# spectrum_analyzer.net
KiCad netlist of a schematic drawn in EAGLE
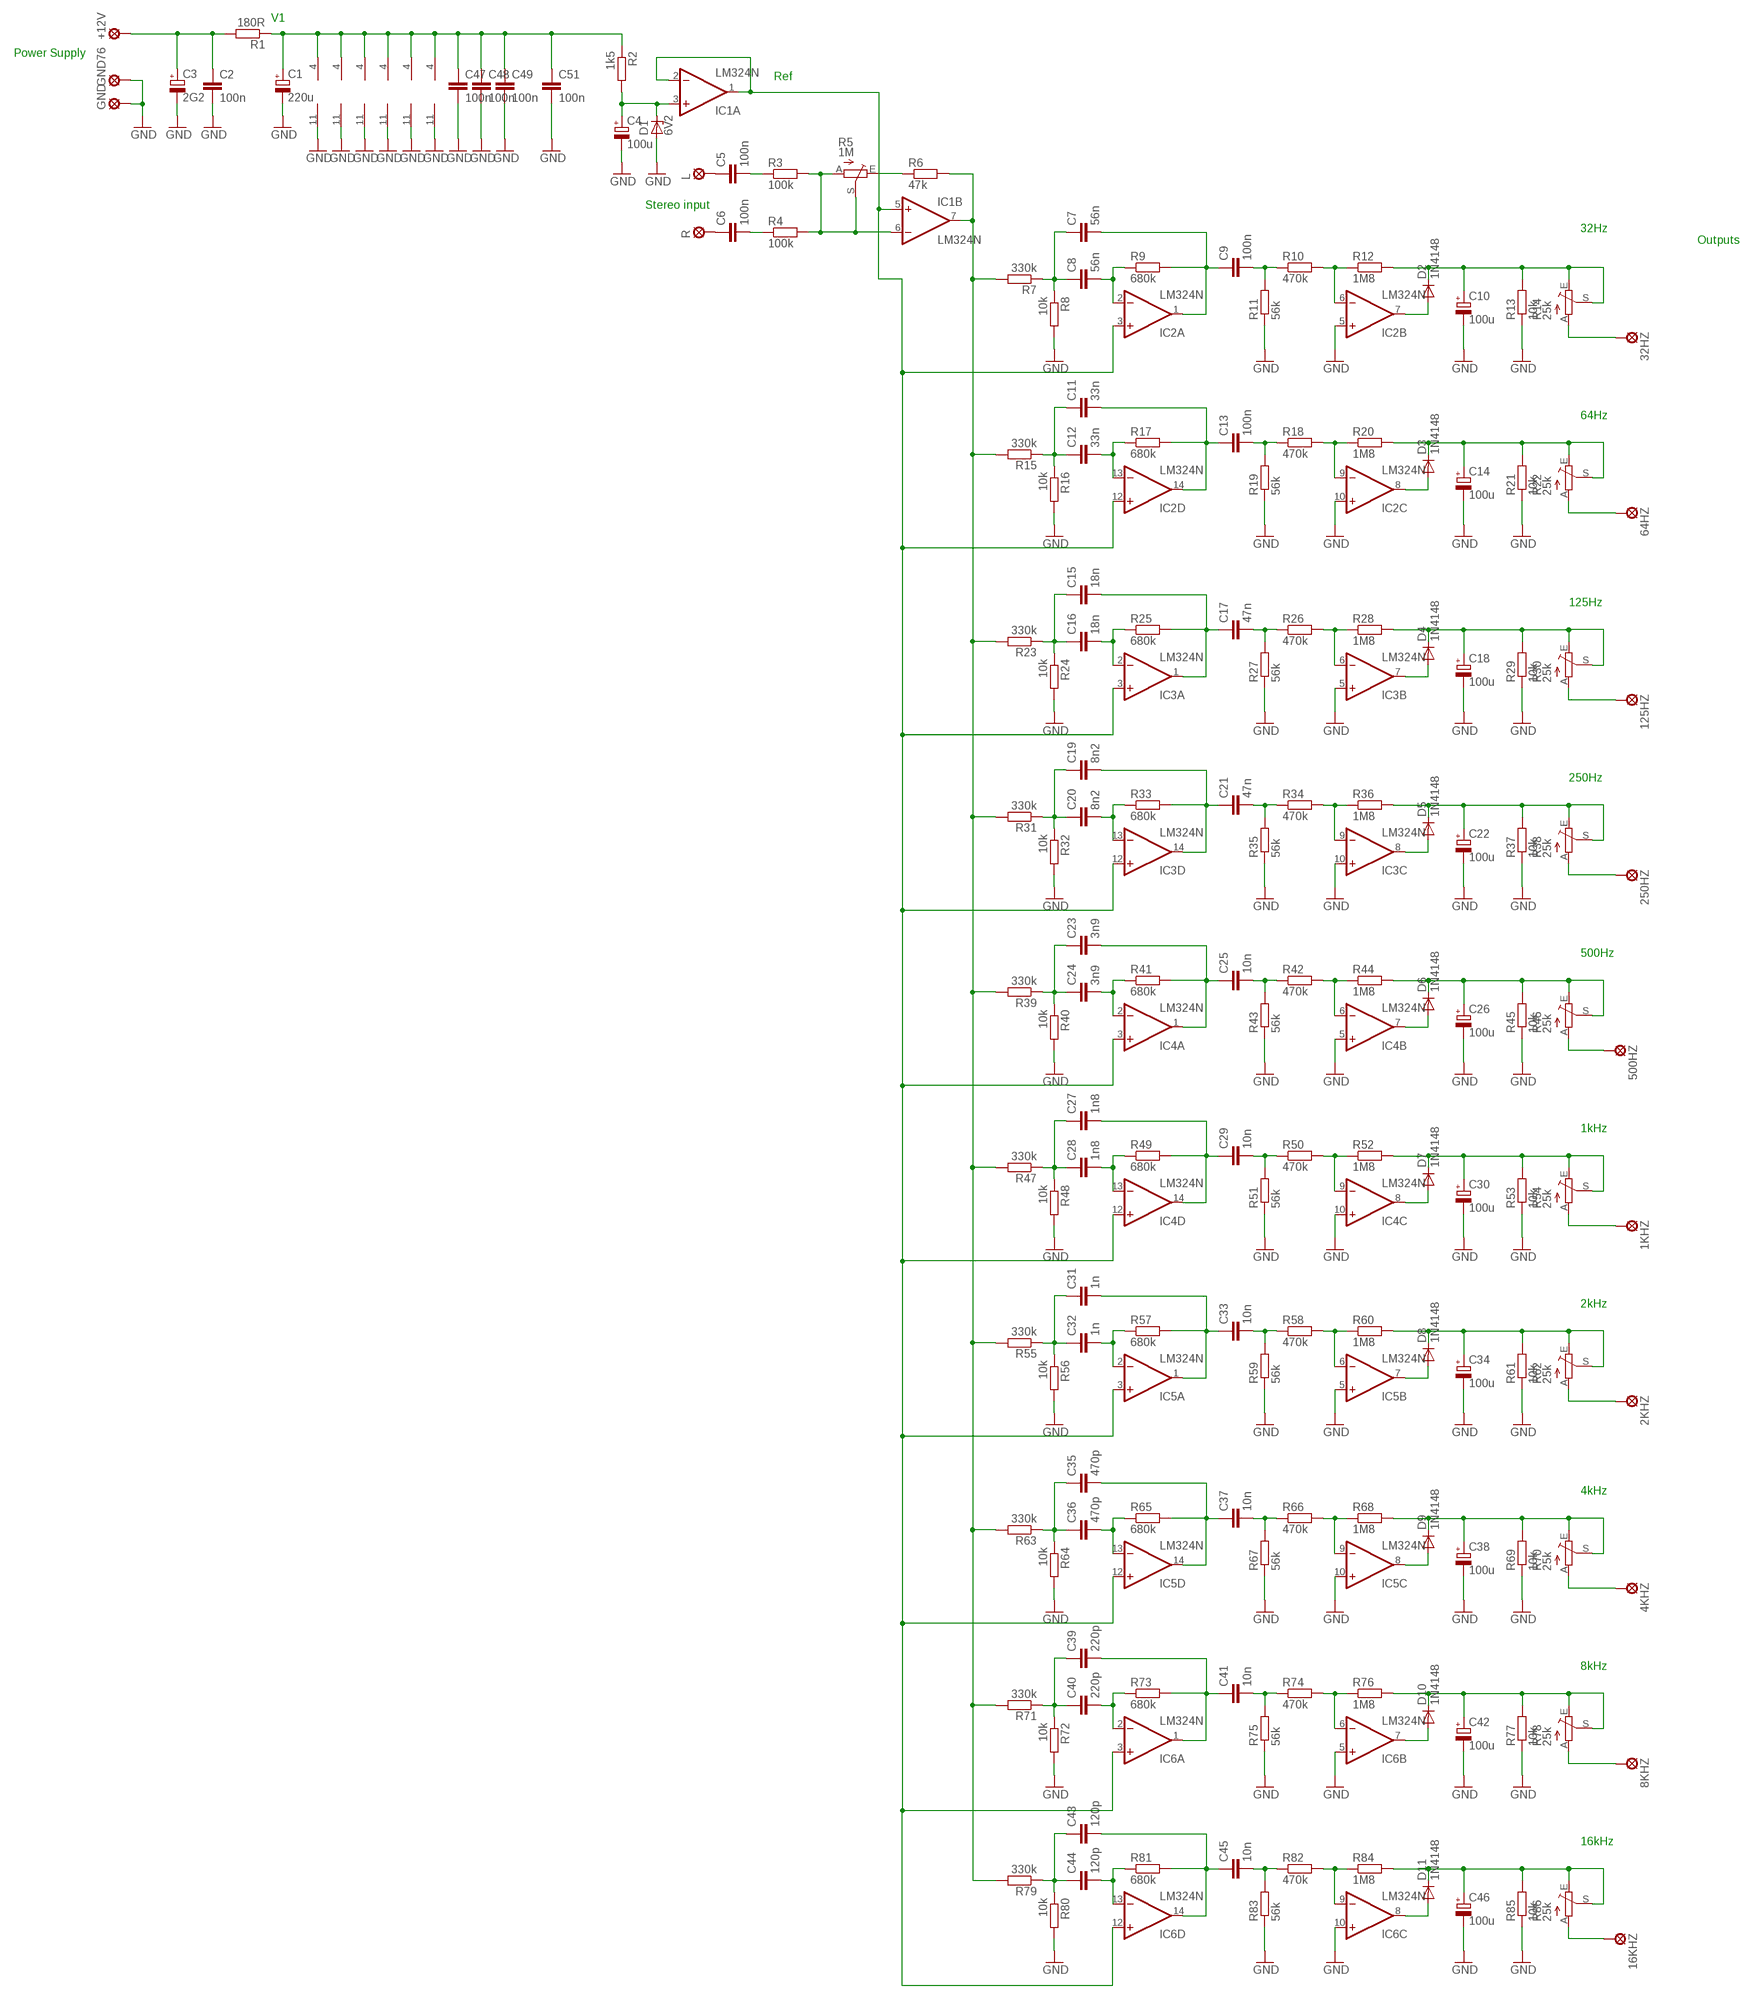
[diagram p0: schematic, sheet 1]

(export (version "E")
  (design (tool "Eeschema 10.0.6"))
  (components
    (comp (ref "+12V")
      (value "LSP10")
      (footprint "eagle-import:LSP10")
      (libsource (lib "eagle-import") (part "LSP10"))
    )
    (comp (ref "1KHZ")
      (value "LSP10")
      (footprint "eagle-import:LSP10")
      (libsource (lib "eagle-import") (part "LSP10"))
    )
    (comp (ref "2KHZ")
      (value "LSP10")
      (footprint "eagle-import:LSP10")
      (libsource (lib "eagle-import") (part "LSP10"))
    )
    (comp (ref "4KHZ")
      (value "LSP10")
      (footprint "eagle-import:LSP10")
      (libsource (lib "eagle-import") (part "LSP10"))
    )
    (comp (ref "8KHZ")
      (value "LSP10")
      (footprint "eagle-import:LSP10")
      (libsource (lib "eagle-import") (part "LSP10"))
    )
    (comp (ref "16KHZ")
      (value "LSP10")
      (footprint "eagle-import:LSP10")
      (libsource (lib "eagle-import") (part "LSP10"))
    )
    (comp (ref "32HZ")
      (value "LSP10")
      (footprint "eagle-import:LSP10")
      (libsource (lib "eagle-import") (part "LSP10"))
    )
    (comp (ref "64HZ")
      (value "LSP10")
      (footprint "eagle-import:LSP10")
      (libsource (lib "eagle-import") (part "LSP10"))
    )
    (comp (ref "125HZ")
      (value "LSP10")
      (footprint "eagle-import:LSP10")
      (libsource (lib "eagle-import") (part "LSP10"))
    )
    (comp (ref "250HZ")
      (value "LSP10")
      (footprint "eagle-import:LSP10")
      (libsource (lib "eagle-import") (part "LSP10"))
    )
    (comp (ref "500HZ")
      (value "LSP10")
      (footprint "eagle-import:LSP10")
      (libsource (lib "eagle-import") (part "LSP10"))
    )
    (comp (ref "C1")
      (value "220u")
      (footprint "eagle-import:E2,5-7")
      (libsource (lib "eagle-import") (part "CPOL-EUE2.5-7"))
    )
    (comp (ref "C2")
      (value "100n")
      (footprint "eagle-import:C050-025X075")
      (libsource (lib "eagle-import") (part "C-EU050-025X075"))
    )
    (comp (ref "C3")
      (value "2G2")
      (footprint "eagle-import:E5-10,5")
      (libsource (lib "eagle-import") (part "CPOL-EUE5-10.5"))
    )
    (comp (ref "C4")
      (value "100u")
      (footprint "eagle-import:E2,5-7")
      (libsource (lib "eagle-import") (part "CPOL-EUE2.5-7"))
    )
    (comp (ref "C5")
      (value "100n")
      (footprint "eagle-import:C050-025X075")
      (libsource (lib "eagle-import") (part "C-EU050-025X075"))
    )
    (comp (ref "C6")
      (value "100n")
      (footprint "eagle-import:C050-025X075")
      (libsource (lib "eagle-import") (part "C-EU050-025X075"))
    )
    (comp (ref "C7")
      (value "56n")
      (footprint "eagle-import:C050-025X075")
      (libsource (lib "eagle-import") (part "C-EU050-025X075"))
    )
    (comp (ref "C8")
      (value "56n")
      (footprint "eagle-import:C050-025X075")
      (libsource (lib "eagle-import") (part "C-EU050-025X075"))
    )
    (comp (ref "C9")
      (value "100n")
      (footprint "eagle-import:C050-025X075")
      (libsource (lib "eagle-import") (part "C-EU050-025X075"))
    )
    (comp (ref "C10")
      (value "100u")
      (footprint "eagle-import:E2,5-7")
      (libsource (lib "eagle-import") (part "CPOL-EUE2.5-7"))
    )
    (comp (ref "C11")
      (value "33n")
      (footprint "eagle-import:C050-025X075")
      (libsource (lib "eagle-import") (part "C-EU050-025X075"))
    )
    (comp (ref "C12")
      (value "33n")
      (footprint "eagle-import:C050-025X075")
      (libsource (lib "eagle-import") (part "C-EU050-025X075"))
    )
    (comp (ref "C13")
      (value "100n")
      (footprint "eagle-import:C050-025X075")
      (libsource (lib "eagle-import") (part "C-EU050-025X075"))
    )
    (comp (ref "C14")
      (value "100u")
      (footprint "eagle-import:E2,5-7")
      (libsource (lib "eagle-import") (part "CPOL-EUE2.5-7"))
    )
    (comp (ref "C15")
      (value "18n")
      (footprint "eagle-import:C050-025X075")
      (libsource (lib "eagle-import") (part "C-EU050-025X075"))
    )
    (comp (ref "C16")
      (value "18n")
      (footprint "eagle-import:C050-025X075")
      (libsource (lib "eagle-import") (part "C-EU050-025X075"))
    )
    (comp (ref "C17")
      (value "47n")
      (footprint "eagle-import:C050-025X075")
      (libsource (lib "eagle-import") (part "C-EU050-025X075"))
    )
    (comp (ref "C18")
      (value "100u")
      (footprint "eagle-import:E2,5-7")
      (libsource (lib "eagle-import") (part "CPOL-EUE2.5-7"))
    )
    (comp (ref "C19")
      (value "8n2")
      (footprint "eagle-import:C050-025X075")
      (libsource (lib "eagle-import") (part "C-EU050-025X075"))
    )
    (comp (ref "C20")
      (value "8n2")
      (footprint "eagle-import:C050-025X075")
      (libsource (lib "eagle-import") (part "C-EU050-025X075"))
    )
    (comp (ref "C21")
      (value "47n")
      (footprint "eagle-import:C050-025X075")
      (libsource (lib "eagle-import") (part "C-EU050-025X075"))
    )
    (comp (ref "C22")
      (value "100u")
      (footprint "eagle-import:E2,5-7")
      (libsource (lib "eagle-import") (part "CPOL-EUE2.5-7"))
    )
    (comp (ref "C23")
      (value "3n9")
      (footprint "eagle-import:C050-025X075")
      (libsource (lib "eagle-import") (part "C-EU050-025X075"))
    )
    (comp (ref "C24")
      (value "3n9")
      (footprint "eagle-import:C050-025X075")
      (libsource (lib "eagle-import") (part "C-EU050-025X075"))
    )
    (comp (ref "C25")
      (value "10n")
      (footprint "eagle-import:C050-025X075")
      (libsource (lib "eagle-import") (part "C-EU050-025X075"))
    )
    (comp (ref "C26")
      (value "100u")
      (footprint "eagle-import:E2,5-7")
      (libsource (lib "eagle-import") (part "CPOL-EUE2.5-7"))
    )
    (comp (ref "C27")
      (value "1n8")
      (footprint "eagle-import:C050-025X075")
      (libsource (lib "eagle-import") (part "C-EU050-025X075"))
    )
    (comp (ref "C28")
      (value "1n8")
      (footprint "eagle-import:C050-025X075")
      (libsource (lib "eagle-import") (part "C-EU050-025X075"))
    )
    (comp (ref "C29")
      (value "10n")
      (footprint "eagle-import:C050-025X075")
      (libsource (lib "eagle-import") (part "C-EU050-025X075"))
    )
    (comp (ref "C30")
      (value "100u")
      (footprint "eagle-import:E2,5-7")
      (libsource (lib "eagle-import") (part "CPOL-EUE2.5-7"))
    )
    (comp (ref "C31")
      (value "1n")
      (footprint "eagle-import:C050-025X075")
      (libsource (lib "eagle-import") (part "C-EU050-025X075"))
    )
    (comp (ref "C32")
      (value "1n")
      (footprint "eagle-import:C050-025X075")
      (libsource (lib "eagle-import") (part "C-EU050-025X075"))
    )
    (comp (ref "C33")
      (value "10n")
      (footprint "eagle-import:C050-025X075")
      (libsource (lib "eagle-import") (part "C-EU050-025X075"))
    )
    (comp (ref "C34")
      (value "100u")
      (footprint "eagle-import:E2,5-7")
      (libsource (lib "eagle-import") (part "CPOL-EUE2.5-7"))
    )
    (comp (ref "C35")
      (value "470p")
      (footprint "eagle-import:C050-025X075")
      (libsource (lib "eagle-import") (part "C-EU050-025X075"))
    )
    (comp (ref "C36")
      (value "470p")
      (footprint "eagle-import:C050-025X075")
      (libsource (lib "eagle-import") (part "C-EU050-025X075"))
    )
    (comp (ref "C37")
      (value "10n")
      (footprint "eagle-import:C050-025X075")
      (libsource (lib "eagle-import") (part "C-EU050-025X075"))
    )
    (comp (ref "C38")
      (value "100u")
      (footprint "eagle-import:E2,5-7")
      (libsource (lib "eagle-import") (part "CPOL-EUE2.5-7"))
    )
    (comp (ref "C39")
      (value "220p")
      (footprint "eagle-import:C050-025X075")
      (libsource (lib "eagle-import") (part "C-EU050-025X075"))
    )
    (comp (ref "C40")
      (value "220p")
      (footprint "eagle-import:C050-025X075")
      (libsource (lib "eagle-import") (part "C-EU050-025X075"))
    )
    (comp (ref "C41")
      (value "10n")
      (footprint "eagle-import:C050-025X075")
      (libsource (lib "eagle-import") (part "C-EU050-025X075"))
    )
    (comp (ref "C42")
      (value "100u")
      (footprint "eagle-import:E2,5-7")
      (libsource (lib "eagle-import") (part "CPOL-EUE2.5-7"))
    )
    (comp (ref "C43")
      (value "120p")
      (footprint "eagle-import:C050-025X075")
      (libsource (lib "eagle-import") (part "C-EU050-025X075"))
    )
    (comp (ref "C44")
      (value "120p")
      (footprint "eagle-import:C050-025X075")
      (libsource (lib "eagle-import") (part "C-EU050-025X075"))
    )
    (comp (ref "C45")
      (value "10n")
      (footprint "eagle-import:C050-025X075")
      (libsource (lib "eagle-import") (part "C-EU050-025X075"))
    )
    (comp (ref "C46")
      (value "100u")
      (footprint "eagle-import:E2,5-7")
      (libsource (lib "eagle-import") (part "CPOL-EUE2.5-7"))
    )
    (comp (ref "C47")
      (value "100n")
      (footprint "eagle-import:C050-025X075")
      (libsource (lib "eagle-import") (part "C-EU050-025X075"))
    )
    (comp (ref "C48")
      (value "100n")
      (footprint "eagle-import:C050-025X075")
      (libsource (lib "eagle-import") (part "C-EU050-025X075"))
    )
    (comp (ref "C49")
      (value "100n")
      (footprint "eagle-import:C050-025X075")
      (libsource (lib "eagle-import") (part "C-EU050-025X075"))
    )
    (comp (ref "C51")
      (value "100n")
      (footprint "eagle-import:C050-025X075")
      (libsource (lib "eagle-import") (part "C-EU050-025X075"))
    )
    (comp (ref "D1")
      (value "6V2")
      (footprint "eagle-import:DO35Z10")
      (libsource (lib "eagle-import") (part "1N821"))
    )
    (comp (ref "D2")
      (value "1N4148")
      (footprint "eagle-import:DO35-10")
      (libsource (lib "eagle-import") (part "1N4148DO35-10"))
    )
    (comp (ref "D3")
      (value "1N4148")
      (footprint "eagle-import:DO35-10")
      (libsource (lib "eagle-import") (part "1N4148DO35-10"))
    )
    (comp (ref "D4")
      (value "1N4148")
      (footprint "eagle-import:DO35-10")
      (libsource (lib "eagle-import") (part "1N4148DO35-10"))
    )
    (comp (ref "D5")
      (value "1N4148")
      (footprint "eagle-import:DO35-10")
      (libsource (lib "eagle-import") (part "1N4148DO35-10"))
    )
    (comp (ref "D6")
      (value "1N4148")
      (footprint "eagle-import:DO35-10")
      (libsource (lib "eagle-import") (part "1N4148DO35-10"))
    )
    (comp (ref "D7")
      (value "1N4148")
      (footprint "eagle-import:DO35-10")
      (libsource (lib "eagle-import") (part "1N4148DO35-10"))
    )
    (comp (ref "D8")
      (value "1N4148")
      (footprint "eagle-import:DO35-10")
      (libsource (lib "eagle-import") (part "1N4148DO35-10"))
    )
    (comp (ref "D9")
      (value "1N4148")
      (footprint "eagle-import:DO35-10")
      (libsource (lib "eagle-import") (part "1N4148DO35-10"))
    )
    (comp (ref "D10")
      (value "1N4148")
      (footprint "eagle-import:DO35-10")
      (libsource (lib "eagle-import") (part "1N4148DO35-10"))
    )
    (comp (ref "D11")
      (value "1N4148")
      (footprint "eagle-import:DO35-10")
      (libsource (lib "eagle-import") (part "1N4148DO35-10"))
    )
    (comp (ref "GND")
      (value "LSP10")
      (footprint "eagle-import:LSP10")
      (libsource (lib "eagle-import") (part "LSP10"))
    )
    (comp (ref "GND76")
      (value "LSP10")
      (footprint "eagle-import:LSP10")
      (libsource (lib "eagle-import") (part "LSP10"))
    )
    (comp (ref "IC1")
      (value "LM324N")
      (footprint "eagle-import:DIL14")
      (libsource (lib "eagle-import") (part "LM324N"))
    )
    (comp (ref "IC2")
      (value "LM324N")
      (footprint "eagle-import:DIL14")
      (libsource (lib "eagle-import") (part "LM324N"))
    )
    (comp (ref "IC3")
      (value "LM324N")
      (footprint "eagle-import:DIL14")
      (libsource (lib "eagle-import") (part "LM324N"))
    )
    (comp (ref "IC4")
      (value "LM324N")
      (footprint "eagle-import:DIL14")
      (libsource (lib "eagle-import") (part "LM324N"))
    )
    (comp (ref "IC5")
      (value "LM324N")
      (footprint "eagle-import:DIL14")
      (libsource (lib "eagle-import") (part "LM324N"))
    )
    (comp (ref "IC6")
      (value "LM324N")
      (footprint "eagle-import:DIL14")
      (libsource (lib "eagle-import") (part "LM324N"))
    )
    (comp (ref "L")
      (value "LSP10")
      (footprint "eagle-import:LSP10")
      (libsource (lib "eagle-import") (part "LSP10"))
    )
    (comp (ref "R")
      (value "LSP10")
      (footprint "eagle-import:LSP10")
      (libsource (lib "eagle-import") (part "LSP10"))
    )
    (comp (ref "R1")
      (value "180R")
      (footprint "eagle-import:0207_10")
      (libsource (lib "eagle-import") (part "R-EU_0207/10"))
    )
    (comp (ref "R2")
      (value "1k5")
      (footprint "eagle-import:0207_10")
      (libsource (lib "eagle-import") (part "R-EU_0207/10"))
    )
    (comp (ref "R3")
      (value "100k")
      (footprint "eagle-import:0207_10")
      (libsource (lib "eagle-import") (part "R-EU_0207/10"))
    )
    (comp (ref "R4")
      (value "100k")
      (footprint "eagle-import:0207_10")
      (libsource (lib "eagle-import") (part "R-EU_0207/10"))
    )
    (comp (ref "R5")
      (value "1M")
      (footprint "eagle-import:CA6V")
      (libsource (lib "eagle-import") (part "TRIM_EU-CA6V"))
    )
    (comp (ref "R6")
      (value "47k")
      (footprint "eagle-import:0207_10")
      (libsource (lib "eagle-import") (part "R-EU_0207/10"))
    )
    (comp (ref "R7")
      (value "330k")
      (footprint "eagle-import:0207_10")
      (libsource (lib "eagle-import") (part "R-EU_0207/10"))
    )
    (comp (ref "R8")
      (value "10k")
      (footprint "eagle-import:0207_10")
      (libsource (lib "eagle-import") (part "R-EU_0207/10"))
    )
    (comp (ref "R9")
      (value "680k")
      (footprint "eagle-import:0207_10")
      (libsource (lib "eagle-import") (part "R-EU_0207/10"))
    )
    (comp (ref "R10")
      (value "470k")
      (footprint "eagle-import:0207_10")
      (libsource (lib "eagle-import") (part "R-EU_0207/10"))
    )
    (comp (ref "R11")
      (value "56k")
      (footprint "eagle-import:0207_10")
      (libsource (lib "eagle-import") (part "R-EU_0207/10"))
    )
    (comp (ref "R12")
      (value "1M8")
      (footprint "eagle-import:0207_10")
      (libsource (lib "eagle-import") (part "R-EU_0207/10"))
    )
    (comp (ref "R13")
      (value "10k")
      (footprint "eagle-import:0207_10")
      (libsource (lib "eagle-import") (part "R-EU_0207/10"))
    )
    (comp (ref "R14")
      (value "25k")
      (footprint "eagle-import:CA6V")
      (libsource (lib "eagle-import") (part "TRIM_EU-CA6V"))
    )
    (comp (ref "R15")
      (value "330k")
      (footprint "eagle-import:0207_10")
      (libsource (lib "eagle-import") (part "R-EU_0207/10"))
    )
    (comp (ref "R16")
      (value "10k")
      (footprint "eagle-import:0207_10")
      (libsource (lib "eagle-import") (part "R-EU_0207/10"))
    )
    (comp (ref "R17")
      (value "680k")
      (footprint "eagle-import:0207_10")
      (libsource (lib "eagle-import") (part "R-EU_0207/10"))
    )
    (comp (ref "R18")
      (value "470k")
      (footprint "eagle-import:0207_10")
      (libsource (lib "eagle-import") (part "R-EU_0207/10"))
    )
    (comp (ref "R19")
      (value "56k")
      (footprint "eagle-import:0207_10")
      (libsource (lib "eagle-import") (part "R-EU_0207/10"))
    )
    (comp (ref "R20")
      (value "1M8")
      (footprint "eagle-import:0207_10")
      (libsource (lib "eagle-import") (part "R-EU_0207/10"))
    )
    (comp (ref "R21")
      (value "10k")
      (footprint "eagle-import:0207_10")
      (libsource (lib "eagle-import") (part "R-EU_0207/10"))
    )
    (comp (ref "R22")
      (value "25k")
      (footprint "eagle-import:CA6V")
      (libsource (lib "eagle-import") (part "TRIM_EU-CA6V"))
    )
    (comp (ref "R23")
      (value "330k")
      (footprint "eagle-import:0207_10")
      (libsource (lib "eagle-import") (part "R-EU_0207/10"))
    )
    (comp (ref "R24")
      (value "10k")
      (footprint "eagle-import:0207_10")
      (libsource (lib "eagle-import") (part "R-EU_0207/10"))
    )
    (comp (ref "R25")
      (value "680k")
      (footprint "eagle-import:0207_10")
      (libsource (lib "eagle-import") (part "R-EU_0207/10"))
    )
    (comp (ref "R26")
      (value "470k")
      (footprint "eagle-import:0207_10")
      (libsource (lib "eagle-import") (part "R-EU_0207/10"))
    )
    (comp (ref "R27")
      (value "56k")
      (footprint "eagle-import:0207_10")
      (libsource (lib "eagle-import") (part "R-EU_0207/10"))
    )
    (comp (ref "R28")
      (value "1M8")
      (footprint "eagle-import:0207_10")
      (libsource (lib "eagle-import") (part "R-EU_0207/10"))
    )
    (comp (ref "R29")
      (value "10k")
      (footprint "eagle-import:0207_10")
      (libsource (lib "eagle-import") (part "R-EU_0207/10"))
    )
    (comp (ref "R30")
      (value "25k")
      (footprint "eagle-import:CA6V")
      (libsource (lib "eagle-import") (part "TRIM_EU-CA6V"))
    )
    (comp (ref "R31")
      (value "330k")
      (footprint "eagle-import:0207_10")
      (libsource (lib "eagle-import") (part "R-EU_0207/10"))
    )
    (comp (ref "R32")
      (value "10k")
      (footprint "eagle-import:0207_10")
      (libsource (lib "eagle-import") (part "R-EU_0207/10"))
    )
    (comp (ref "R33")
      (value "680k")
      (footprint "eagle-import:0207_10")
      (libsource (lib "eagle-import") (part "R-EU_0207/10"))
    )
    (comp (ref "R34")
      (value "470k")
      (footprint "eagle-import:0207_10")
      (libsource (lib "eagle-import") (part "R-EU_0207/10"))
    )
    (comp (ref "R35")
      (value "56k")
      (footprint "eagle-import:0207_10")
      (libsource (lib "eagle-import") (part "R-EU_0207/10"))
    )
    (comp (ref "R36")
      (value "1M8")
      (footprint "eagle-import:0207_10")
      (libsource (lib "eagle-import") (part "R-EU_0207/10"))
    )
    (comp (ref "R37")
      (value "10k")
      (footprint "eagle-import:0207_10")
      (libsource (lib "eagle-import") (part "R-EU_0207/10"))
    )
    (comp (ref "R38")
      (value "25k")
      (footprint "eagle-import:CA6V")
      (libsource (lib "eagle-import") (part "TRIM_EU-CA6V"))
    )
    (comp (ref "R39")
      (value "330k")
      (footprint "eagle-import:0207_10")
      (libsource (lib "eagle-import") (part "R-EU_0207/10"))
    )
    (comp (ref "R40")
      (value "10k")
      (footprint "eagle-import:0207_10")
      (libsource (lib "eagle-import") (part "R-EU_0207/10"))
    )
    (comp (ref "R41")
      (value "680k")
      (footprint "eagle-import:0207_10")
      (libsource (lib "eagle-import") (part "R-EU_0207/10"))
    )
    (comp (ref "R42")
      (value "470k")
      (footprint "eagle-import:0207_10")
      (libsource (lib "eagle-import") (part "R-EU_0207/10"))
    )
    (comp (ref "R43")
      (value "56k")
      (footprint "eagle-import:0207_10")
      (libsource (lib "eagle-import") (part "R-EU_0207/10"))
    )
    (comp (ref "R44")
      (value "1M8")
      (footprint "eagle-import:0207_10")
      (libsource (lib "eagle-import") (part "R-EU_0207/10"))
    )
    (comp (ref "R45")
      (value "10k")
      (footprint "eagle-import:0207_10")
      (libsource (lib "eagle-import") (part "R-EU_0207/10"))
    )
    (comp (ref "R46")
      (value "25k")
      (footprint "eagle-import:CA6V")
      (libsource (lib "eagle-import") (part "TRIM_EU-CA6V"))
    )
    (comp (ref "R47")
      (value "330k")
      (footprint "eagle-import:0207_10")
      (libsource (lib "eagle-import") (part "R-EU_0207/10"))
    )
    (comp (ref "R48")
      (value "10k")
      (footprint "eagle-import:0207_10")
      (libsource (lib "eagle-import") (part "R-EU_0207/10"))
    )
    (comp (ref "R49")
      (value "680k")
      (footprint "eagle-import:0207_10")
      (libsource (lib "eagle-import") (part "R-EU_0207/10"))
    )
    (comp (ref "R50")
      (value "470k")
      (footprint "eagle-import:0207_10")
      (libsource (lib "eagle-import") (part "R-EU_0207/10"))
    )
    (comp (ref "R51")
      (value "56k")
      (footprint "eagle-import:0207_10")
      (libsource (lib "eagle-import") (part "R-EU_0207/10"))
    )
    (comp (ref "R52")
      (value "1M8")
      (footprint "eagle-import:0207_10")
      (libsource (lib "eagle-import") (part "R-EU_0207/10"))
    )
    (comp (ref "R53")
      (value "10k")
      (footprint "eagle-import:0207_10")
      (libsource (lib "eagle-import") (part "R-EU_0207/10"))
    )
    (comp (ref "R54")
      (value "25k")
      (footprint "eagle-import:CA6V")
      (libsource (lib "eagle-import") (part "TRIM_EU-CA6V"))
    )
    (comp (ref "R55")
      (value "330k")
      (footprint "eagle-import:0207_10")
      (libsource (lib "eagle-import") (part "R-EU_0207/10"))
    )
    (comp (ref "R56")
      (value "10k")
      (footprint "eagle-import:0207_10")
      (libsource (lib "eagle-import") (part "R-EU_0207/10"))
    )
    (comp (ref "R57")
      (value "680k")
      (footprint "eagle-import:0207_10")
      (libsource (lib "eagle-import") (part "R-EU_0207/10"))
    )
    (comp (ref "R58")
      (value "470k")
      (footprint "eagle-import:0207_10")
      (libsource (lib "eagle-import") (part "R-EU_0207/10"))
    )
    (comp (ref "R59")
      (value "56k")
      (footprint "eagle-import:0207_10")
      (libsource (lib "eagle-import") (part "R-EU_0207/10"))
    )
    (comp (ref "R60")
      (value "1M8")
      (footprint "eagle-import:0207_10")
      (libsource (lib "eagle-import") (part "R-EU_0207/10"))
    )
    (comp (ref "R61")
      (value "10k")
      (footprint "eagle-import:0207_10")
      (libsource (lib "eagle-import") (part "R-EU_0207/10"))
    )
    (comp (ref "R62")
      (value "25k")
      (footprint "eagle-import:CA6V")
      (libsource (lib "eagle-import") (part "TRIM_EU-CA6V"))
    )
    (comp (ref "R63")
      (value "330k")
      (footprint "eagle-import:0207_10")
      (libsource (lib "eagle-import") (part "R-EU_0207/10"))
    )
    (comp (ref "R64")
      (value "10k")
      (footprint "eagle-import:0207_10")
      (libsource (lib "eagle-import") (part "R-EU_0207/10"))
    )
    (comp (ref "R65")
      (value "680k")
      (footprint "eagle-import:0207_10")
      (libsource (lib "eagle-import") (part "R-EU_0207/10"))
    )
    (comp (ref "R66")
      (value "470k")
      (footprint "eagle-import:0207_10")
      (libsource (lib "eagle-import") (part "R-EU_0207/10"))
    )
    (comp (ref "R67")
      (value "56k")
      (footprint "eagle-import:0207_10")
      (libsource (lib "eagle-import") (part "R-EU_0207/10"))
    )
    (comp (ref "R68")
      (value "1M8")
      (footprint "eagle-import:0207_10")
      (libsource (lib "eagle-import") (part "R-EU_0207/10"))
    )
    (comp (ref "R69")
      (value "10k")
      (footprint "eagle-import:0207_10")
      (libsource (lib "eagle-import") (part "R-EU_0207/10"))
    )
    (comp (ref "R70")
      (value "25k")
      (footprint "eagle-import:CA6V")
      (libsource (lib "eagle-import") (part "TRIM_EU-CA6V"))
    )
    (comp (ref "R71")
      (value "330k")
      (footprint "eagle-import:0207_10")
      (libsource (lib "eagle-import") (part "R-EU_0207/10"))
    )
    (comp (ref "R72")
      (value "10k")
      (footprint "eagle-import:0207_10")
      (libsource (lib "eagle-import") (part "R-EU_0207/10"))
    )
    (comp (ref "R73")
      (value "680k")
      (footprint "eagle-import:0207_10")
      (libsource (lib "eagle-import") (part "R-EU_0207/10"))
    )
    (comp (ref "R74")
      (value "470k")
      (footprint "eagle-import:0207_10")
      (libsource (lib "eagle-import") (part "R-EU_0207/10"))
    )
    (comp (ref "R75")
      (value "56k")
      (footprint "eagle-import:0207_10")
      (libsource (lib "eagle-import") (part "R-EU_0207/10"))
    )
    (comp (ref "R76")
      (value "1M8")
      (footprint "eagle-import:0207_10")
      (libsource (lib "eagle-import") (part "R-EU_0207/10"))
    )
    (comp (ref "R77")
      (value "10k")
      (footprint "eagle-import:0207_10")
      (libsource (lib "eagle-import") (part "R-EU_0207/10"))
    )
    (comp (ref "R78")
      (value "25k")
      (footprint "eagle-import:CA6V")
      (libsource (lib "eagle-import") (part "TRIM_EU-CA6V"))
    )
    (comp (ref "R79")
      (value "330k")
      (footprint "eagle-import:0207_10")
      (libsource (lib "eagle-import") (part "R-EU_0207/10"))
    )
    (comp (ref "R80")
      (value "10k")
      (footprint "eagle-import:0207_10")
      (libsource (lib "eagle-import") (part "R-EU_0207/10"))
    )
    (comp (ref "R81")
      (value "680k")
      (footprint "eagle-import:0207_10")
      (libsource (lib "eagle-import") (part "R-EU_0207/10"))
    )
    (comp (ref "R82")
      (value "470k")
      (footprint "eagle-import:0207_10")
      (libsource (lib "eagle-import") (part "R-EU_0207/10"))
    )
    (comp (ref "R83")
      (value "56k")
      (footprint "eagle-import:0207_10")
      (libsource (lib "eagle-import") (part "R-EU_0207/10"))
    )
    (comp (ref "R84")
      (value "1M8")
      (footprint "eagle-import:0207_10")
      (libsource (lib "eagle-import") (part "R-EU_0207/10"))
    )
    (comp (ref "R85")
      (value "10k")
      (footprint "eagle-import:0207_10")
      (libsource (lib "eagle-import") (part "R-EU_0207/10"))
    )
    (comp (ref "R86")
      (value "25k")
      (footprint "eagle-import:CA6V")
      (libsource (lib "eagle-import") (part "TRIM_EU-CA6V"))
    )
  )
  (nets
    (net (code "1") (name "GND") (class "Default")
      (node (ref "C1") (pin "-") (pinfunction "-_-") (pintype "passive"))
      (node (ref "C10") (pin "-") (pinfunction "-_-") (pintype "passive"))
      (node (ref "C14") (pin "-") (pinfunction "-_-") (pintype "passive"))
      (node (ref "C18") (pin "-") (pinfunction "-_-") (pintype "passive"))
      (node (ref "C2") (pin "2") (pinfunction "2_2") (pintype "passive"))
      (node (ref "C22") (pin "-") (pinfunction "-_-") (pintype "passive"))
      (node (ref "C26") (pin "-") (pinfunction "-_-") (pintype "passive"))
      (node (ref "C3") (pin "-") (pinfunction "-_-") (pintype "passive"))
      (node (ref "C30") (pin "-") (pinfunction "-_-") (pintype "passive"))
      (node (ref "C34") (pin "-") (pinfunction "-_-") (pintype "passive"))
      (node (ref "C38") (pin "-") (pinfunction "-_-") (pintype "passive"))
      (node (ref "C4") (pin "-") (pinfunction "-_-") (pintype "passive"))
      (node (ref "C42") (pin "-") (pinfunction "-_-") (pintype "passive"))
      (node (ref "C46") (pin "-") (pinfunction "-_-") (pintype "passive"))
      (node (ref "C47") (pin "2") (pinfunction "2_2") (pintype "passive"))
      (node (ref "C48") (pin "2") (pinfunction "2_2") (pintype "passive"))
      (node (ref "C49") (pin "2") (pinfunction "2_2") (pintype "passive"))
      (node (ref "C51") (pin "2") (pinfunction "2_2") (pintype "passive"))
      (node (ref "D1") (pin "A") (pinfunction "A_A") (pintype "passive"))
      (node (ref "GND") (pin "MP") (pinfunction "MP_MP") (pintype "passive"))
      (node (ref "GND76") (pin "MP") (pinfunction "MP_MP") (pintype "passive"))
      (node (ref "IC1") (pin "11") (pinfunction "V-_11") (pintype "power_in"))
      (node (ref "IC2") (pin "10") (pinfunction "+IN_10") (pintype "input"))
      (node (ref "IC2") (pin "11") (pinfunction "V-_11") (pintype "power_in"))
      (node (ref "IC2") (pin "5") (pinfunction "+IN_5") (pintype "input"))
      (node (ref "IC3") (pin "10") (pinfunction "+IN_10") (pintype "input"))
      (node (ref "IC3") (pin "11") (pinfunction "V-_11") (pintype "power_in"))
      (node (ref "IC3") (pin "5") (pinfunction "+IN_5") (pintype "input"))
      (node (ref "IC4") (pin "10") (pinfunction "+IN_10") (pintype "input"))
      (node (ref "IC4") (pin "11") (pinfunction "V-_11") (pintype "power_in"))
      (node (ref "IC4") (pin "5") (pinfunction "+IN_5") (pintype "input"))
      (node (ref "IC5") (pin "10") (pinfunction "+IN_10") (pintype "input"))
      (node (ref "IC5") (pin "11") (pinfunction "V-_11") (pintype "power_in"))
      (node (ref "IC5") (pin "5") (pinfunction "+IN_5") (pintype "input"))
      (node (ref "IC6") (pin "10") (pinfunction "+IN_10") (pintype "input"))
      (node (ref "IC6") (pin "11") (pinfunction "V-_11") (pintype "power_in"))
      (node (ref "IC6") (pin "5") (pinfunction "+IN_5") (pintype "input"))
      (node (ref "R11") (pin "1") (pinfunction "1_1") (pintype "passive"))
      (node (ref "R13") (pin "1") (pinfunction "1_1") (pintype "passive"))
      (node (ref "R16") (pin "2") (pinfunction "2_2") (pintype "passive"))
      (node (ref "R19") (pin "1") (pinfunction "1_1") (pintype "passive"))
      (node (ref "R21") (pin "1") (pinfunction "1_1") (pintype "passive"))
      (node (ref "R24") (pin "2") (pinfunction "2_2") (pintype "passive"))
      (node (ref "R27") (pin "1") (pinfunction "1_1") (pintype "passive"))
      (node (ref "R29") (pin "1") (pinfunction "1_1") (pintype "passive"))
      (node (ref "R32") (pin "2") (pinfunction "2_2") (pintype "passive"))
      (node (ref "R35") (pin "1") (pinfunction "1_1") (pintype "passive"))
      (node (ref "R37") (pin "1") (pinfunction "1_1") (pintype "passive"))
      (node (ref "R40") (pin "2") (pinfunction "2_2") (pintype "passive"))
      (node (ref "R43") (pin "1") (pinfunction "1_1") (pintype "passive"))
      (node (ref "R45") (pin "1") (pinfunction "1_1") (pintype "passive"))
      (node (ref "R48") (pin "2") (pinfunction "2_2") (pintype "passive"))
      (node (ref "R51") (pin "1") (pinfunction "1_1") (pintype "passive"))
      (node (ref "R53") (pin "1") (pinfunction "1_1") (pintype "passive"))
      (node (ref "R56") (pin "2") (pinfunction "2_2") (pintype "passive"))
      (node (ref "R59") (pin "1") (pinfunction "1_1") (pintype "passive"))
      (node (ref "R61") (pin "1") (pinfunction "1_1") (pintype "passive"))
      (node (ref "R64") (pin "2") (pinfunction "2_2") (pintype "passive"))
      (node (ref "R67") (pin "1") (pinfunction "1_1") (pintype "passive"))
      (node (ref "R69") (pin "1") (pinfunction "1_1") (pintype "passive"))
      (node (ref "R72") (pin "2") (pinfunction "2_2") (pintype "passive"))
      (node (ref "R75") (pin "1") (pinfunction "1_1") (pintype "passive"))
      (node (ref "R77") (pin "1") (pinfunction "1_1") (pintype "passive"))
      (node (ref "R8") (pin "2") (pinfunction "2_2") (pintype "passive"))
      (node (ref "R80") (pin "2") (pinfunction "2_2") (pintype "passive"))
      (node (ref "R83") (pin "1") (pinfunction "1_1") (pintype "passive"))
      (node (ref "R85") (pin "1") (pinfunction "1_1") (pintype "passive"))
    )
    (net (code "2") (name "Net-(+12V-PadMP)") (class "Default")
      (node (ref "+12V") (pin "MP") (pinfunction "MP_MP") (pintype "passive"))
      (node (ref "C2") (pin "1") (pinfunction "1_1") (pintype "passive"))
      (node (ref "C3") (pin "+") (pinfunction "+_+") (pintype "passive"))
      (node (ref "R1") (pin "2") (pinfunction "2_2") (pintype "passive"))
    )
    (net (code "3") (name "Net-(1KHZ-PadMP)") (class "Default")
      (node (ref "1KHZ") (pin "MP") (pinfunction "MP_MP") (pintype "passive"))
      (node (ref "R54") (pin "A") (pinfunction "A_A") (pintype "passive"))
    )
    (net (code "4") (name "Net-(2KHZ-PadMP)") (class "Default")
      (node (ref "2KHZ") (pin "MP") (pinfunction "MP_MP") (pintype "passive"))
      (node (ref "R62") (pin "A") (pinfunction "A_A") (pintype "passive"))
    )
    (net (code "5") (name "Net-(4KHZ-PadMP)") (class "Default")
      (node (ref "4KHZ") (pin "MP") (pinfunction "MP_MP") (pintype "passive"))
      (node (ref "R70") (pin "A") (pinfunction "A_A") (pintype "passive"))
    )
    (net (code "6") (name "Net-(8KHZ-PadMP)") (class "Default")
      (node (ref "8KHZ") (pin "MP") (pinfunction "MP_MP") (pintype "passive"))
      (node (ref "R78") (pin "A") (pinfunction "A_A") (pintype "passive"))
    )
    (net (code "7") (name "Net-(16KHZ-PadMP)") (class "Default")
      (node (ref "16KHZ") (pin "MP") (pinfunction "MP_MP") (pintype "passive"))
      (node (ref "R86") (pin "A") (pinfunction "A_A") (pintype "passive"))
    )
    (net (code "8") (name "Net-(32HZ-PadMP)") (class "Default")
      (node (ref "32HZ") (pin "MP") (pinfunction "MP_MP") (pintype "passive"))
      (node (ref "R14") (pin "A") (pinfunction "A_A") (pintype "passive"))
    )
    (net (code "9") (name "Net-(64HZ-PadMP)") (class "Default")
      (node (ref "64HZ") (pin "MP") (pinfunction "MP_MP") (pintype "passive"))
      (node (ref "R22") (pin "A") (pinfunction "A_A") (pintype "passive"))
    )
    (net (code "10") (name "Net-(125HZ-PadMP)") (class "Default")
      (node (ref "125HZ") (pin "MP") (pinfunction "MP_MP") (pintype "passive"))
      (node (ref "R30") (pin "A") (pinfunction "A_A") (pintype "passive"))
    )
    (net (code "11") (name "Net-(250HZ-PadMP)") (class "Default")
      (node (ref "250HZ") (pin "MP") (pinfunction "MP_MP") (pintype "passive"))
      (node (ref "R38") (pin "A") (pinfunction "A_A") (pintype "passive"))
    )
    (net (code "12") (name "Net-(500HZ-PadMP)") (class "Default")
      (node (ref "500HZ") (pin "MP") (pinfunction "MP_MP") (pintype "passive"))
      (node (ref "R46") (pin "A") (pinfunction "A_A") (pintype "passive"))
    )
    (net (code "13") (name "Net-(C5-Pad1)") (class "Default")
      (node (ref "C5") (pin "1") (pinfunction "1_1") (pintype "passive"))
      (node (ref "L") (pin "MP") (pinfunction "MP_MP") (pintype "passive"))
    )
    (net (code "14") (name "Net-(C5-Pad2)") (class "Default")
      (node (ref "C5") (pin "2") (pinfunction "2_2") (pintype "passive"))
      (node (ref "R3") (pin "1") (pinfunction "1_1") (pintype "passive"))
    )
    (net (code "15") (name "Net-(C6-Pad1)") (class "Default")
      (node (ref "C6") (pin "1") (pinfunction "1_1") (pintype "passive"))
      (node (ref "R") (pin "MP") (pinfunction "MP_MP") (pintype "passive"))
    )
    (net (code "16") (name "Net-(C6-Pad2)") (class "Default")
      (node (ref "C6") (pin "2") (pinfunction "2_2") (pintype "passive"))
      (node (ref "R4") (pin "1") (pinfunction "1_1") (pintype "passive"))
    )
    (net (code "17") (name "Net-(C7-Pad1)") (class "Default")
      (node (ref "C7") (pin "1") (pinfunction "1_1") (pintype "passive"))
      (node (ref "C8") (pin "1") (pinfunction "1_1") (pintype "passive"))
      (node (ref "R7") (pin "1") (pinfunction "1_1") (pintype "passive"))
      (node (ref "R8") (pin "1") (pinfunction "1_1") (pintype "passive"))
    )
    (net (code "18") (name "Net-(C9-Pad2)") (class "Default")
      (node (ref "C9") (pin "2") (pinfunction "2_2") (pintype "passive"))
      (node (ref "R10") (pin "1") (pinfunction "1_1") (pintype "passive"))
      (node (ref "R11") (pin "2") (pinfunction "2_2") (pintype "passive"))
    )
    (net (code "19") (name "Net-(C10-Pad+)") (class "Default")
      (node (ref "C10") (pin "+") (pinfunction "+_+") (pintype "passive"))
      (node (ref "D2") (pin "C") (pinfunction "C_C") (pintype "passive"))
      (node (ref "R12") (pin "2") (pinfunction "2_2") (pintype "passive"))
      (node (ref "R13") (pin "2") (pinfunction "2_2") (pintype "passive"))
      (node (ref "R14") (pin "E") (pinfunction "E_E") (pintype "passive"))
      (node (ref "R14") (pin "S") (pinfunction "S_S") (pintype "passive"))
    )
    (net (code "20") (name "Net-(C11-Pad1)") (class "Default")
      (node (ref "C11") (pin "1") (pinfunction "1_1") (pintype "passive"))
      (node (ref "C12") (pin "1") (pinfunction "1_1") (pintype "passive"))
      (node (ref "R15") (pin "1") (pinfunction "1_1") (pintype "passive"))
      (node (ref "R16") (pin "1") (pinfunction "1_1") (pintype "passive"))
    )
    (net (code "21") (name "Net-(C13-Pad2)") (class "Default")
      (node (ref "C13") (pin "2") (pinfunction "2_2") (pintype "passive"))
      (node (ref "R18") (pin "1") (pinfunction "1_1") (pintype "passive"))
      (node (ref "R19") (pin "2") (pinfunction "2_2") (pintype "passive"))
    )
    (net (code "22") (name "Net-(C14-Pad+)") (class "Default")
      (node (ref "C14") (pin "+") (pinfunction "+_+") (pintype "passive"))
      (node (ref "D3") (pin "C") (pinfunction "C_C") (pintype "passive"))
      (node (ref "R20") (pin "2") (pinfunction "2_2") (pintype "passive"))
      (node (ref "R21") (pin "2") (pinfunction "2_2") (pintype "passive"))
      (node (ref "R22") (pin "E") (pinfunction "E_E") (pintype "passive"))
      (node (ref "R22") (pin "S") (pinfunction "S_S") (pintype "passive"))
    )
    (net (code "23") (name "Net-(C15-Pad1)") (class "Default")
      (node (ref "C15") (pin "1") (pinfunction "1_1") (pintype "passive"))
      (node (ref "C16") (pin "1") (pinfunction "1_1") (pintype "passive"))
      (node (ref "R23") (pin "1") (pinfunction "1_1") (pintype "passive"))
      (node (ref "R24") (pin "1") (pinfunction "1_1") (pintype "passive"))
    )
    (net (code "24") (name "Net-(C17-Pad2)") (class "Default")
      (node (ref "C17") (pin "2") (pinfunction "2_2") (pintype "passive"))
      (node (ref "R26") (pin "1") (pinfunction "1_1") (pintype "passive"))
      (node (ref "R27") (pin "2") (pinfunction "2_2") (pintype "passive"))
    )
    (net (code "25") (name "Net-(C18-Pad+)") (class "Default")
      (node (ref "C18") (pin "+") (pinfunction "+_+") (pintype "passive"))
      (node (ref "D4") (pin "C") (pinfunction "C_C") (pintype "passive"))
      (node (ref "R28") (pin "2") (pinfunction "2_2") (pintype "passive"))
      (node (ref "R29") (pin "2") (pinfunction "2_2") (pintype "passive"))
      (node (ref "R30") (pin "E") (pinfunction "E_E") (pintype "passive"))
      (node (ref "R30") (pin "S") (pinfunction "S_S") (pintype "passive"))
    )
    (net (code "26") (name "Net-(C19-Pad1)") (class "Default")
      (node (ref "C19") (pin "1") (pinfunction "1_1") (pintype "passive"))
      (node (ref "C20") (pin "1") (pinfunction "1_1") (pintype "passive"))
      (node (ref "R31") (pin "1") (pinfunction "1_1") (pintype "passive"))
      (node (ref "R32") (pin "1") (pinfunction "1_1") (pintype "passive"))
    )
    (net (code "27") (name "Net-(C21-Pad2)") (class "Default")
      (node (ref "C21") (pin "2") (pinfunction "2_2") (pintype "passive"))
      (node (ref "R34") (pin "1") (pinfunction "1_1") (pintype "passive"))
      (node (ref "R35") (pin "2") (pinfunction "2_2") (pintype "passive"))
    )
    (net (code "28") (name "Net-(C22-Pad+)") (class "Default")
      (node (ref "C22") (pin "+") (pinfunction "+_+") (pintype "passive"))
      (node (ref "D5") (pin "C") (pinfunction "C_C") (pintype "passive"))
      (node (ref "R36") (pin "2") (pinfunction "2_2") (pintype "passive"))
      (node (ref "R37") (pin "2") (pinfunction "2_2") (pintype "passive"))
      (node (ref "R38") (pin "E") (pinfunction "E_E") (pintype "passive"))
      (node (ref "R38") (pin "S") (pinfunction "S_S") (pintype "passive"))
    )
    (net (code "29") (name "Net-(C23-Pad1)") (class "Default")
      (node (ref "C23") (pin "1") (pinfunction "1_1") (pintype "passive"))
      (node (ref "C24") (pin "1") (pinfunction "1_1") (pintype "passive"))
      (node (ref "R39") (pin "1") (pinfunction "1_1") (pintype "passive"))
      (node (ref "R40") (pin "1") (pinfunction "1_1") (pintype "passive"))
    )
    (net (code "30") (name "Net-(C25-Pad2)") (class "Default")
      (node (ref "C25") (pin "2") (pinfunction "2_2") (pintype "passive"))
      (node (ref "R42") (pin "1") (pinfunction "1_1") (pintype "passive"))
      (node (ref "R43") (pin "2") (pinfunction "2_2") (pintype "passive"))
    )
    (net (code "31") (name "Net-(C26-Pad+)") (class "Default")
      (node (ref "C26") (pin "+") (pinfunction "+_+") (pintype "passive"))
      (node (ref "D6") (pin "C") (pinfunction "C_C") (pintype "passive"))
      (node (ref "R44") (pin "2") (pinfunction "2_2") (pintype "passive"))
      (node (ref "R45") (pin "2") (pinfunction "2_2") (pintype "passive"))
      (node (ref "R46") (pin "E") (pinfunction "E_E") (pintype "passive"))
      (node (ref "R46") (pin "S") (pinfunction "S_S") (pintype "passive"))
    )
    (net (code "32") (name "Net-(C27-Pad1)") (class "Default")
      (node (ref "C27") (pin "1") (pinfunction "1_1") (pintype "passive"))
      (node (ref "C28") (pin "1") (pinfunction "1_1") (pintype "passive"))
      (node (ref "R47") (pin "1") (pinfunction "1_1") (pintype "passive"))
      (node (ref "R48") (pin "1") (pinfunction "1_1") (pintype "passive"))
    )
    (net (code "33") (name "Net-(C29-Pad2)") (class "Default")
      (node (ref "C29") (pin "2") (pinfunction "2_2") (pintype "passive"))
      (node (ref "R50") (pin "1") (pinfunction "1_1") (pintype "passive"))
      (node (ref "R51") (pin "2") (pinfunction "2_2") (pintype "passive"))
    )
    (net (code "34") (name "Net-(C30-Pad+)") (class "Default")
      (node (ref "C30") (pin "+") (pinfunction "+_+") (pintype "passive"))
      (node (ref "D7") (pin "C") (pinfunction "C_C") (pintype "passive"))
      (node (ref "R52") (pin "2") (pinfunction "2_2") (pintype "passive"))
      (node (ref "R53") (pin "2") (pinfunction "2_2") (pintype "passive"))
      (node (ref "R54") (pin "E") (pinfunction "E_E") (pintype "passive"))
      (node (ref "R54") (pin "S") (pinfunction "S_S") (pintype "passive"))
    )
    (net (code "35") (name "Net-(C31-Pad1)") (class "Default")
      (node (ref "C31") (pin "1") (pinfunction "1_1") (pintype "passive"))
      (node (ref "C32") (pin "1") (pinfunction "1_1") (pintype "passive"))
      (node (ref "R55") (pin "1") (pinfunction "1_1") (pintype "passive"))
      (node (ref "R56") (pin "1") (pinfunction "1_1") (pintype "passive"))
    )
    (net (code "36") (name "Net-(C33-Pad2)") (class "Default")
      (node (ref "C33") (pin "2") (pinfunction "2_2") (pintype "passive"))
      (node (ref "R58") (pin "1") (pinfunction "1_1") (pintype "passive"))
      (node (ref "R59") (pin "2") (pinfunction "2_2") (pintype "passive"))
    )
    (net (code "37") (name "Net-(C34-Pad+)") (class "Default")
      (node (ref "C34") (pin "+") (pinfunction "+_+") (pintype "passive"))
      (node (ref "D8") (pin "C") (pinfunction "C_C") (pintype "passive"))
      (node (ref "R60") (pin "2") (pinfunction "2_2") (pintype "passive"))
      (node (ref "R61") (pin "2") (pinfunction "2_2") (pintype "passive"))
      (node (ref "R62") (pin "E") (pinfunction "E_E") (pintype "passive"))
      (node (ref "R62") (pin "S") (pinfunction "S_S") (pintype "passive"))
    )
    (net (code "38") (name "Net-(C35-Pad1)") (class "Default")
      (node (ref "C35") (pin "1") (pinfunction "1_1") (pintype "passive"))
      (node (ref "C36") (pin "1") (pinfunction "1_1") (pintype "passive"))
      (node (ref "R63") (pin "1") (pinfunction "1_1") (pintype "passive"))
      (node (ref "R64") (pin "1") (pinfunction "1_1") (pintype "passive"))
    )
    (net (code "39") (name "Net-(C37-Pad2)") (class "Default")
      (node (ref "C37") (pin "2") (pinfunction "2_2") (pintype "passive"))
      (node (ref "R66") (pin "1") (pinfunction "1_1") (pintype "passive"))
      (node (ref "R67") (pin "2") (pinfunction "2_2") (pintype "passive"))
    )
    (net (code "40") (name "Net-(C38-Pad+)") (class "Default")
      (node (ref "C38") (pin "+") (pinfunction "+_+") (pintype "passive"))
      (node (ref "D9") (pin "C") (pinfunction "C_C") (pintype "passive"))
      (node (ref "R68") (pin "2") (pinfunction "2_2") (pintype "passive"))
      (node (ref "R69") (pin "2") (pinfunction "2_2") (pintype "passive"))
      (node (ref "R70") (pin "E") (pinfunction "E_E") (pintype "passive"))
      (node (ref "R70") (pin "S") (pinfunction "S_S") (pintype "passive"))
    )
    (net (code "41") (name "Net-(C39-Pad1)") (class "Default")
      (node (ref "C39") (pin "1") (pinfunction "1_1") (pintype "passive"))
      (node (ref "C40") (pin "1") (pinfunction "1_1") (pintype "passive"))
      (node (ref "R71") (pin "1") (pinfunction "1_1") (pintype "passive"))
      (node (ref "R72") (pin "1") (pinfunction "1_1") (pintype "passive"))
    )
    (net (code "42") (name "Net-(C41-Pad2)") (class "Default")
      (node (ref "C41") (pin "2") (pinfunction "2_2") (pintype "passive"))
      (node (ref "R74") (pin "1") (pinfunction "1_1") (pintype "passive"))
      (node (ref "R75") (pin "2") (pinfunction "2_2") (pintype "passive"))
    )
    (net (code "43") (name "Net-(C42-Pad+)") (class "Default")
      (node (ref "C42") (pin "+") (pinfunction "+_+") (pintype "passive"))
      (node (ref "D10") (pin "C") (pinfunction "C_C") (pintype "passive"))
      (node (ref "R76") (pin "2") (pinfunction "2_2") (pintype "passive"))
      (node (ref "R77") (pin "2") (pinfunction "2_2") (pintype "passive"))
      (node (ref "R78") (pin "E") (pinfunction "E_E") (pintype "passive"))
      (node (ref "R78") (pin "S") (pinfunction "S_S") (pintype "passive"))
    )
    (net (code "44") (name "Net-(C43-Pad1)") (class "Default")
      (node (ref "C43") (pin "1") (pinfunction "1_1") (pintype "passive"))
      (node (ref "C44") (pin "1") (pinfunction "1_1") (pintype "passive"))
      (node (ref "R79") (pin "1") (pinfunction "1_1") (pintype "passive"))
      (node (ref "R80") (pin "1") (pinfunction "1_1") (pintype "passive"))
    )
    (net (code "45") (name "Net-(C45-Pad2)") (class "Default")
      (node (ref "C45") (pin "2") (pinfunction "2_2") (pintype "passive"))
      (node (ref "R82") (pin "1") (pinfunction "1_1") (pintype "passive"))
      (node (ref "R83") (pin "2") (pinfunction "2_2") (pintype "passive"))
    )
    (net (code "46") (name "Net-(C46-Pad+)") (class "Default")
      (node (ref "C46") (pin "+") (pinfunction "+_+") (pintype "passive"))
      (node (ref "D11") (pin "C") (pinfunction "C_C") (pintype "passive"))
      (node (ref "R84") (pin "2") (pinfunction "2_2") (pintype "passive"))
      (node (ref "R85") (pin "2") (pinfunction "2_2") (pintype "passive"))
      (node (ref "R86") (pin "E") (pinfunction "E_E") (pintype "passive"))
      (node (ref "R86") (pin "S") (pinfunction "S_S") (pintype "passive"))
    )
    (net (code "47") (name "Net-(IC1A-+IN)") (class "Default")
      (node (ref "C4") (pin "+") (pinfunction "+_+") (pintype "passive"))
      (node (ref "D1") (pin "C") (pinfunction "C_C") (pintype "passive"))
      (node (ref "IC1") (pin "3") (pinfunction "+IN_3") (pintype "input"))
      (node (ref "R2") (pin "2") (pinfunction "2_2") (pintype "passive"))
    )
    (net (code "48") (name "Net-(IC1A--IN)") (class "Default")
      (node (ref "IC1") (pin "1") (pinfunction "OUT_1") (pintype "output"))
      (node (ref "IC1") (pin "2") (pinfunction "-IN_2") (pintype "input"))
      (node (ref "IC1") (pin "5") (pinfunction "+IN_5") (pintype "input"))
      (node (ref "IC2") (pin "12") (pinfunction "+IN_12") (pintype "input"))
      (node (ref "IC2") (pin "3") (pinfunction "+IN_3") (pintype "input"))
      (node (ref "IC3") (pin "12") (pinfunction "+IN_12") (pintype "input"))
      (node (ref "IC3") (pin "3") (pinfunction "+IN_3") (pintype "input"))
      (node (ref "IC4") (pin "12") (pinfunction "+IN_12") (pintype "input"))
      (node (ref "IC4") (pin "3") (pinfunction "+IN_3") (pintype "input"))
      (node (ref "IC5") (pin "12") (pinfunction "+IN_12") (pintype "input"))
      (node (ref "IC5") (pin "3") (pinfunction "+IN_3") (pintype "input"))
      (node (ref "IC6") (pin "12") (pinfunction "+IN_12") (pintype "input"))
      (node (ref "IC6") (pin "3") (pinfunction "+IN_3") (pintype "input"))
    )
    (net (code "49") (name "Net-(IC1B--IN)") (class "Default")
      (node (ref "IC1") (pin "6") (pinfunction "-IN_6") (pintype "input"))
      (node (ref "R3") (pin "2") (pinfunction "2_2") (pintype "passive"))
      (node (ref "R4") (pin "2") (pinfunction "2_2") (pintype "passive"))
      (node (ref "R5") (pin "A") (pinfunction "A_A") (pintype "passive"))
      (node (ref "R5") (pin "S") (pinfunction "S_S") (pintype "passive"))
    )
    (net (code "50") (name "Net-(IC1B-OUT)") (class "Default")
      (node (ref "IC1") (pin "7") (pinfunction "OUT_7") (pintype "output"))
      (node (ref "R15") (pin "2") (pinfunction "2_2") (pintype "passive"))
      (node (ref "R23") (pin "2") (pinfunction "2_2") (pintype "passive"))
      (node (ref "R31") (pin "2") (pinfunction "2_2") (pintype "passive"))
      (node (ref "R39") (pin "2") (pinfunction "2_2") (pintype "passive"))
      (node (ref "R47") (pin "2") (pinfunction "2_2") (pintype "passive"))
      (node (ref "R55") (pin "2") (pinfunction "2_2") (pintype "passive"))
      (node (ref "R6") (pin "2") (pinfunction "2_2") (pintype "passive"))
      (node (ref "R63") (pin "2") (pinfunction "2_2") (pintype "passive"))
      (node (ref "R7") (pin "2") (pinfunction "2_2") (pintype "passive"))
      (node (ref "R71") (pin "2") (pinfunction "2_2") (pintype "passive"))
      (node (ref "R79") (pin "2") (pinfunction "2_2") (pintype "passive"))
    )
    (net (code "51") (name "Net-(IC1E-V+)") (class "Default")
      (node (ref "C1") (pin "+") (pinfunction "+_+") (pintype "passive"))
      (node (ref "C47") (pin "1") (pinfunction "1_1") (pintype "passive"))
      (node (ref "C48") (pin "1") (pinfunction "1_1") (pintype "passive"))
      (node (ref "C49") (pin "1") (pinfunction "1_1") (pintype "passive"))
      (node (ref "C51") (pin "1") (pinfunction "1_1") (pintype "passive"))
      (node (ref "IC1") (pin "4") (pinfunction "V+_4") (pintype "power_in"))
      (node (ref "IC2") (pin "4") (pinfunction "V+_4") (pintype "power_in"))
      (node (ref "IC3") (pin "4") (pinfunction "V+_4") (pintype "power_in"))
      (node (ref "IC4") (pin "4") (pinfunction "V+_4") (pintype "power_in"))
      (node (ref "IC5") (pin "4") (pinfunction "V+_4") (pintype "power_in"))
      (node (ref "IC6") (pin "4") (pinfunction "V+_4") (pintype "power_in"))
      (node (ref "R1") (pin "1") (pinfunction "1_1") (pintype "passive"))
      (node (ref "R2") (pin "1") (pinfunction "1_1") (pintype "passive"))
    )
    (net (code "52") (name "Net-(IC2A--IN)") (class "Default")
      (node (ref "C8") (pin "2") (pinfunction "2_2") (pintype "passive"))
      (node (ref "IC2") (pin "2") (pinfunction "-IN_2") (pintype "input"))
      (node (ref "R9") (pin "1") (pinfunction "1_1") (pintype "passive"))
    )
    (net (code "53") (name "Net-(IC2A-OUT)") (class "Default")
      (node (ref "C7") (pin "2") (pinfunction "2_2") (pintype "passive"))
      (node (ref "C9") (pin "1") (pinfunction "1_1") (pintype "passive"))
      (node (ref "IC2") (pin "1") (pinfunction "OUT_1") (pintype "output"))
      (node (ref "R9") (pin "2") (pinfunction "2_2") (pintype "passive"))
    )
    (net (code "54") (name "Net-(IC2B--IN)") (class "Default")
      (node (ref "IC2") (pin "6") (pinfunction "-IN_6") (pintype "input"))
      (node (ref "R10") (pin "2") (pinfunction "2_2") (pintype "passive"))
      (node (ref "R12") (pin "1") (pinfunction "1_1") (pintype "passive"))
    )
    (net (code "55") (name "Net-(IC2B-OUT)") (class "Default")
      (node (ref "D2") (pin "A") (pinfunction "A_A") (pintype "passive"))
      (node (ref "IC2") (pin "7") (pinfunction "OUT_7") (pintype "output"))
    )
    (net (code "56") (name "Net-(IC2C--IN)") (class "Default")
      (node (ref "IC2") (pin "9") (pinfunction "-IN_9") (pintype "input"))
      (node (ref "R18") (pin "2") (pinfunction "2_2") (pintype "passive"))
      (node (ref "R20") (pin "1") (pinfunction "1_1") (pintype "passive"))
    )
    (net (code "57") (name "Net-(IC2C-OUT)") (class "Default")
      (node (ref "D3") (pin "A") (pinfunction "A_A") (pintype "passive"))
      (node (ref "IC2") (pin "8") (pinfunction "OUT_8") (pintype "output"))
    )
    (net (code "58") (name "Net-(IC2D--IN)") (class "Default")
      (node (ref "C12") (pin "2") (pinfunction "2_2") (pintype "passive"))
      (node (ref "IC2") (pin "13") (pinfunction "-IN_13") (pintype "input"))
      (node (ref "R17") (pin "1") (pinfunction "1_1") (pintype "passive"))
    )
    (net (code "59") (name "Net-(IC2D-OUT)") (class "Default")
      (node (ref "C11") (pin "2") (pinfunction "2_2") (pintype "passive"))
      (node (ref "C13") (pin "1") (pinfunction "1_1") (pintype "passive"))
      (node (ref "IC2") (pin "14") (pinfunction "OUT_14") (pintype "output"))
      (node (ref "R17") (pin "2") (pinfunction "2_2") (pintype "passive"))
    )
    (net (code "60") (name "Net-(IC3A--IN)") (class "Default")
      (node (ref "C16") (pin "2") (pinfunction "2_2") (pintype "passive"))
      (node (ref "IC3") (pin "2") (pinfunction "-IN_2") (pintype "input"))
      (node (ref "R25") (pin "1") (pinfunction "1_1") (pintype "passive"))
    )
    (net (code "61") (name "Net-(IC3A-OUT)") (class "Default")
      (node (ref "C15") (pin "2") (pinfunction "2_2") (pintype "passive"))
      (node (ref "C17") (pin "1") (pinfunction "1_1") (pintype "passive"))
      (node (ref "IC3") (pin "1") (pinfunction "OUT_1") (pintype "output"))
      (node (ref "R25") (pin "2") (pinfunction "2_2") (pintype "passive"))
    )
    (net (code "62") (name "Net-(IC3B--IN)") (class "Default")
      (node (ref "IC3") (pin "6") (pinfunction "-IN_6") (pintype "input"))
      (node (ref "R26") (pin "2") (pinfunction "2_2") (pintype "passive"))
      (node (ref "R28") (pin "1") (pinfunction "1_1") (pintype "passive"))
    )
    (net (code "63") (name "Net-(IC3B-OUT)") (class "Default")
      (node (ref "D4") (pin "A") (pinfunction "A_A") (pintype "passive"))
      (node (ref "IC3") (pin "7") (pinfunction "OUT_7") (pintype "output"))
    )
    (net (code "64") (name "Net-(IC3C--IN)") (class "Default")
      (node (ref "IC3") (pin "9") (pinfunction "-IN_9") (pintype "input"))
      (node (ref "R34") (pin "2") (pinfunction "2_2") (pintype "passive"))
      (node (ref "R36") (pin "1") (pinfunction "1_1") (pintype "passive"))
    )
    (net (code "65") (name "Net-(IC3C-OUT)") (class "Default")
      (node (ref "D5") (pin "A") (pinfunction "A_A") (pintype "passive"))
      (node (ref "IC3") (pin "8") (pinfunction "OUT_8") (pintype "output"))
    )
    (net (code "66") (name "Net-(IC3D--IN)") (class "Default")
      (node (ref "C20") (pin "2") (pinfunction "2_2") (pintype "passive"))
      (node (ref "IC3") (pin "13") (pinfunction "-IN_13") (pintype "input"))
      (node (ref "R33") (pin "1") (pinfunction "1_1") (pintype "passive"))
    )
    (net (code "67") (name "Net-(IC3D-OUT)") (class "Default")
      (node (ref "C19") (pin "2") (pinfunction "2_2") (pintype "passive"))
      (node (ref "C21") (pin "1") (pinfunction "1_1") (pintype "passive"))
      (node (ref "IC3") (pin "14") (pinfunction "OUT_14") (pintype "output"))
      (node (ref "R33") (pin "2") (pinfunction "2_2") (pintype "passive"))
    )
    (net (code "68") (name "Net-(IC4A--IN)") (class "Default")
      (node (ref "C24") (pin "2") (pinfunction "2_2") (pintype "passive"))
      (node (ref "IC4") (pin "2") (pinfunction "-IN_2") (pintype "input"))
      (node (ref "R41") (pin "1") (pinfunction "1_1") (pintype "passive"))
    )
    (net (code "69") (name "Net-(IC4A-OUT)") (class "Default")
      (node (ref "C23") (pin "2") (pinfunction "2_2") (pintype "passive"))
      (node (ref "C25") (pin "1") (pinfunction "1_1") (pintype "passive"))
      (node (ref "IC4") (pin "1") (pinfunction "OUT_1") (pintype "output"))
      (node (ref "R41") (pin "2") (pinfunction "2_2") (pintype "passive"))
    )
    (net (code "70") (name "Net-(IC4B--IN)") (class "Default")
      (node (ref "IC4") (pin "6") (pinfunction "-IN_6") (pintype "input"))
      (node (ref "R42") (pin "2") (pinfunction "2_2") (pintype "passive"))
      (node (ref "R44") (pin "1") (pinfunction "1_1") (pintype "passive"))
    )
    (net (code "71") (name "Net-(IC4B-OUT)") (class "Default")
      (node (ref "D6") (pin "A") (pinfunction "A_A") (pintype "passive"))
      (node (ref "IC4") (pin "7") (pinfunction "OUT_7") (pintype "output"))
    )
    (net (code "72") (name "Net-(IC4C--IN)") (class "Default")
      (node (ref "IC4") (pin "9") (pinfunction "-IN_9") (pintype "input"))
      (node (ref "R50") (pin "2") (pinfunction "2_2") (pintype "passive"))
      (node (ref "R52") (pin "1") (pinfunction "1_1") (pintype "passive"))
    )
    (net (code "73") (name "Net-(IC4C-OUT)") (class "Default")
      (node (ref "D7") (pin "A") (pinfunction "A_A") (pintype "passive"))
      (node (ref "IC4") (pin "8") (pinfunction "OUT_8") (pintype "output"))
    )
    (net (code "74") (name "Net-(IC4D--IN)") (class "Default")
      (node (ref "C28") (pin "2") (pinfunction "2_2") (pintype "passive"))
      (node (ref "IC4") (pin "13") (pinfunction "-IN_13") (pintype "input"))
      (node (ref "R49") (pin "1") (pinfunction "1_1") (pintype "passive"))
    )
    (net (code "75") (name "Net-(IC4D-OUT)") (class "Default")
      (node (ref "C27") (pin "2") (pinfunction "2_2") (pintype "passive"))
      (node (ref "C29") (pin "1") (pinfunction "1_1") (pintype "passive"))
      (node (ref "IC4") (pin "14") (pinfunction "OUT_14") (pintype "output"))
      (node (ref "R49") (pin "2") (pinfunction "2_2") (pintype "passive"))
    )
    (net (code "76") (name "Net-(IC5A--IN)") (class "Default")
      (node (ref "C32") (pin "2") (pinfunction "2_2") (pintype "passive"))
      (node (ref "IC5") (pin "2") (pinfunction "-IN_2") (pintype "input"))
      (node (ref "R57") (pin "1") (pinfunction "1_1") (pintype "passive"))
    )
    (net (code "77") (name "Net-(IC5A-OUT)") (class "Default")
      (node (ref "C31") (pin "2") (pinfunction "2_2") (pintype "passive"))
      (node (ref "C33") (pin "1") (pinfunction "1_1") (pintype "passive"))
      (node (ref "IC5") (pin "1") (pinfunction "OUT_1") (pintype "output"))
      (node (ref "R57") (pin "2") (pinfunction "2_2") (pintype "passive"))
    )
    (net (code "78") (name "Net-(IC5B--IN)") (class "Default")
      (node (ref "IC5") (pin "6") (pinfunction "-IN_6") (pintype "input"))
      (node (ref "R58") (pin "2") (pinfunction "2_2") (pintype "passive"))
      (node (ref "R60") (pin "1") (pinfunction "1_1") (pintype "passive"))
    )
    (net (code "79") (name "Net-(IC5B-OUT)") (class "Default")
      (node (ref "D8") (pin "A") (pinfunction "A_A") (pintype "passive"))
      (node (ref "IC5") (pin "7") (pinfunction "OUT_7") (pintype "output"))
    )
    (net (code "80") (name "Net-(IC5C--IN)") (class "Default")
      (node (ref "IC5") (pin "9") (pinfunction "-IN_9") (pintype "input"))
      (node (ref "R66") (pin "2") (pinfunction "2_2") (pintype "passive"))
      (node (ref "R68") (pin "1") (pinfunction "1_1") (pintype "passive"))
    )
    (net (code "81") (name "Net-(IC5C-OUT)") (class "Default")
      (node (ref "D9") (pin "A") (pinfunction "A_A") (pintype "passive"))
      (node (ref "IC5") (pin "8") (pinfunction "OUT_8") (pintype "output"))
    )
    (net (code "82") (name "Net-(IC5D--IN)") (class "Default")
      (node (ref "C36") (pin "2") (pinfunction "2_2") (pintype "passive"))
      (node (ref "IC5") (pin "13") (pinfunction "-IN_13") (pintype "input"))
      (node (ref "R65") (pin "1") (pinfunction "1_1") (pintype "passive"))
    )
    (net (code "83") (name "Net-(IC5D-OUT)") (class "Default")
      (node (ref "C35") (pin "2") (pinfunction "2_2") (pintype "passive"))
      (node (ref "C37") (pin "1") (pinfunction "1_1") (pintype "passive"))
      (node (ref "IC5") (pin "14") (pinfunction "OUT_14") (pintype "output"))
      (node (ref "R65") (pin "2") (pinfunction "2_2") (pintype "passive"))
    )
    (net (code "84") (name "Net-(IC6A--IN)") (class "Default")
      (node (ref "C40") (pin "2") (pinfunction "2_2") (pintype "passive"))
      (node (ref "IC6") (pin "2") (pinfunction "-IN_2") (pintype "input"))
      (node (ref "R73") (pin "1") (pinfunction "1_1") (pintype "passive"))
    )
    (net (code "85") (name "Net-(IC6A-OUT)") (class "Default")
      (node (ref "C39") (pin "2") (pinfunction "2_2") (pintype "passive"))
      (node (ref "C41") (pin "1") (pinfunction "1_1") (pintype "passive"))
      (node (ref "IC6") (pin "1") (pinfunction "OUT_1") (pintype "output"))
      (node (ref "R73") (pin "2") (pinfunction "2_2") (pintype "passive"))
    )
    (net (code "86") (name "Net-(IC6B--IN)") (class "Default")
      (node (ref "IC6") (pin "6") (pinfunction "-IN_6") (pintype "input"))
      (node (ref "R74") (pin "2") (pinfunction "2_2") (pintype "passive"))
      (node (ref "R76") (pin "1") (pinfunction "1_1") (pintype "passive"))
    )
    (net (code "87") (name "Net-(IC6B-OUT)") (class "Default")
      (node (ref "D10") (pin "A") (pinfunction "A_A") (pintype "passive"))
      (node (ref "IC6") (pin "7") (pinfunction "OUT_7") (pintype "output"))
    )
    (net (code "88") (name "Net-(IC6C--IN)") (class "Default")
      (node (ref "IC6") (pin "9") (pinfunction "-IN_9") (pintype "input"))
      (node (ref "R82") (pin "2") (pinfunction "2_2") (pintype "passive"))
      (node (ref "R84") (pin "1") (pinfunction "1_1") (pintype "passive"))
    )
    (net (code "89") (name "Net-(IC6C-OUT)") (class "Default")
      (node (ref "D11") (pin "A") (pinfunction "A_A") (pintype "passive"))
      (node (ref "IC6") (pin "8") (pinfunction "OUT_8") (pintype "output"))
    )
    (net (code "90") (name "Net-(IC6D--IN)") (class "Default")
      (node (ref "C44") (pin "2") (pinfunction "2_2") (pintype "passive"))
      (node (ref "IC6") (pin "13") (pinfunction "-IN_13") (pintype "input"))
      (node (ref "R81") (pin "1") (pinfunction "1_1") (pintype "passive"))
    )
    (net (code "91") (name "Net-(IC6D-OUT)") (class "Default")
      (node (ref "C43") (pin "2") (pinfunction "2_2") (pintype "passive"))
      (node (ref "C45") (pin "1") (pinfunction "1_1") (pintype "passive"))
      (node (ref "IC6") (pin "14") (pinfunction "OUT_14") (pintype "output"))
      (node (ref "R81") (pin "2") (pinfunction "2_2") (pintype "passive"))
    )
    (net (code "92") (name "Net-(R5-PadE)") (class "Default")
      (node (ref "R5") (pin "E") (pinfunction "E_E") (pintype "passive"))
      (node (ref "R6") (pin "1") (pinfunction "1_1") (pintype "passive"))
    )
  )
)
